# Transmitter_Schematic.net
KiCad netlist of a schematic drawn in Altium Designer
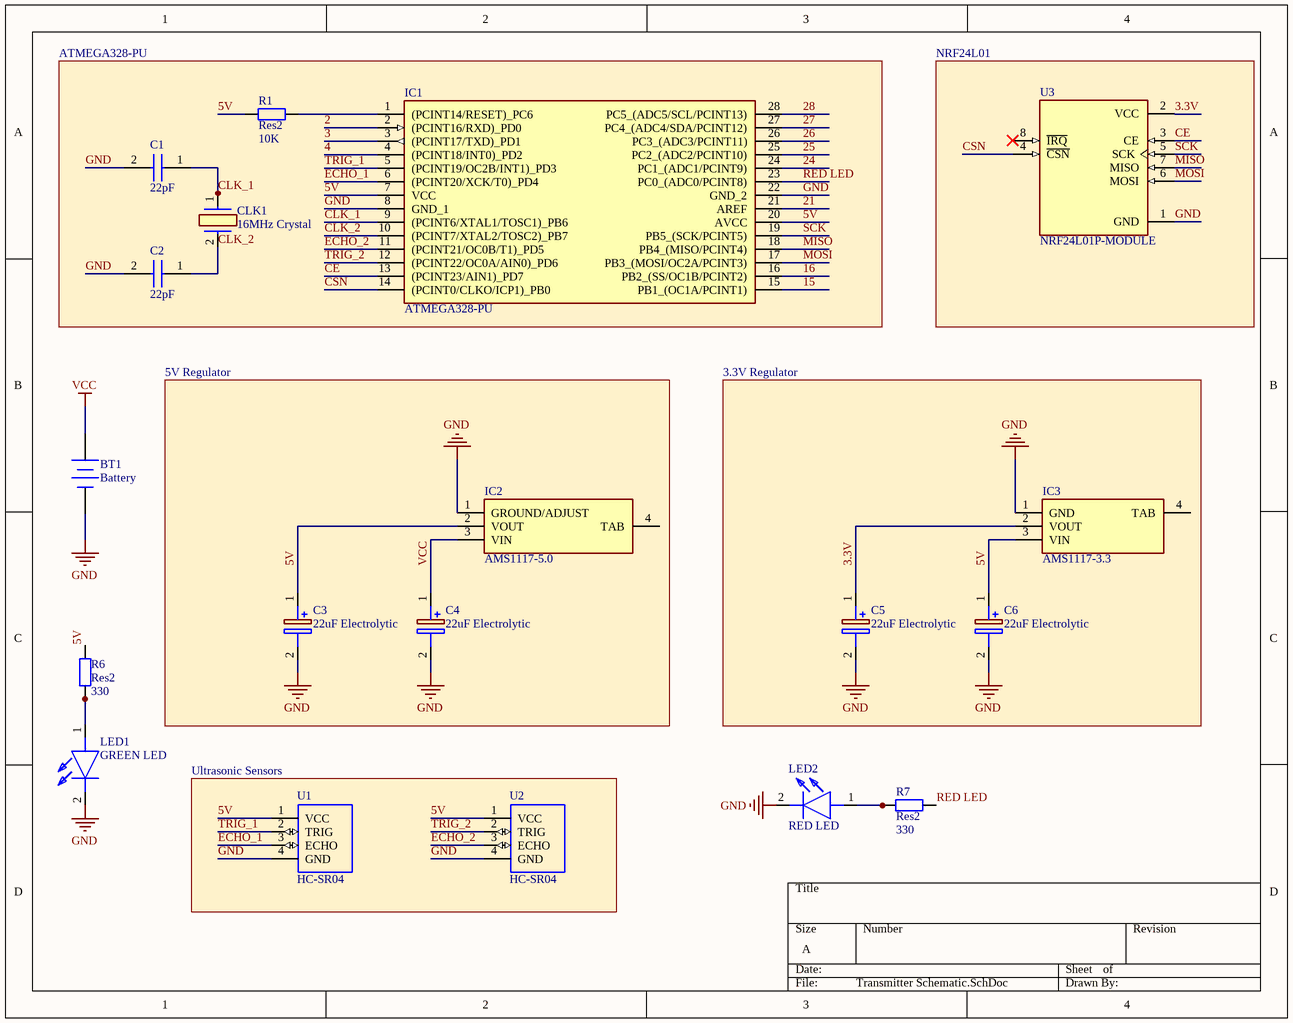
[diagram p0: Transmitter Schematic.SchDoc]

(export (version "E")
  (design (tool "Eeschema 10.0.6"))
  (components
    (comp (ref "BT1")
      (value "Battery")
      (footprint "BAT-2")
      (description "Multicell Battery")
      (fields (field (name "PUBLISHER") "Altium Limited"))
      (libsource (lib "Miscellaneous Devices") (part "Battery"))
    )
    (comp (ref "C1")
      (value "22pF")
      (footprint "SamacSys:S220K25SL0N63L6R")
      (description "Capacitor Ceramic THT")
      (fields
        (field (name "MANUFACTURER_PART_NUMBER") "S220K25SL0N63L6R")
        (field (name "MOUSER PART NUMBER") "594-S220K25SL0N63L6R")
      )
      (libsource (lib "*") (part "S220K25SL0N63L6R"))
    )
    (comp (ref "C2")
      (value "22pF")
      (footprint "SamacSys:S220K25SL0N63L6R")
      (description "Capacitor Ceramic THT")
      (fields
        (field (name "MANUFACTURER_PART_NUMBER") "S220K25SL0N63L6R")
        (field (name "MOUSER PART NUMBER") "594-S220K25SL0N63L6R")
      )
      (libsource (lib "*") (part "S220K25SL0N63L6R"))
    )
    (comp (ref "C3")
      (value "22uF Electrolytic")
      (footprint "SamacSys:CAPPRD250W55D630H1220")
      (description "Capacitor Polarised")
      (fields (field (name "MANUFACTURER_PART_NUMBER") "ECA1EEN220"))
      (libsource (lib "*") (part "ECA1EEN220"))
    )
    (comp (ref "C4")
      (value "22uF Electrolytic")
      (footprint "SamacSys:CAPPRD250W55D630H1220")
      (description "Capacitor Polarised")
      (fields (field (name "MANUFACTURER_PART_NUMBER") "ECA1EEN220"))
      (libsource (lib "*") (part "ECA1EEN220"))
    )
    (comp (ref "C5")
      (value "22uF Electrolytic")
      (footprint "SamacSys:CAPPRD250W55D630H1220")
      (description "Capacitor Polarised")
      (fields (field (name "MANUFACTURER_PART_NUMBER") "ECA1EEN220"))
      (libsource (lib "*") (part "ECA1EEN220"))
    )
    (comp (ref "C6")
      (value "22uF Electrolytic")
      (footprint "SamacSys:CAPPRD250W55D630H1220")
      (description "Capacitor Polarised")
      (fields (field (name "MANUFACTURER_PART_NUMBER") "ECA1EEN220"))
      (libsource (lib "*") (part "ECA1EEN220"))
    )
    (comp (ref "CLK1")
      (value "16MHz Crystal")
      (footprint "SamacSys:LFXTAL036391Bulk")
      (description "Crystal or Oscillator")
      (fields
        (field (name "MANUFACTURER_PART_NUMBER") "LFXTAL036391Bulk")
        (field (name "MOUSER PART NUMBER") "449-LFXTAL036391BULK")
      )
      (libsource (lib "*") (part "LFXTAL036391Bulk"))
    )
    (comp (ref "IC1")
      (value "ATMEGA328-PU")
      (footprint "SamacSys:DIP1016W53P254L3468H457Q28N")
      (description "Integrated Circuit")
      (fields (field (name "MOUSER PART NUMBER") "556-ATMEGA328-PU"))
      (libsource (lib "*") (part "ATMEGA328-PU"))
    )
    (comp (ref "IC2")
      (value "AMS1117-5.0")
      (footprint "SamacSys:SOT229P700X180-4N")
      (description "Integrated Circuit")
      (libsource (lib "*") (part "AMS1117-5.0"))
    )
    (comp (ref "IC3")
      (value "AMS1117-3.3")
      (footprint "SamacSys:SOT229P700X180-4N")
      (description "Integrated Circuit")
      (libsource (lib "*") (part "AMS1117-3.3"))
    )
    (comp (ref "LED1")
      (value "GREEN LED")
      (footprint "SamacSys:125410SURTS530A3")
      (description "LED")
      (fields (field (name "MANUFACTURER_PART_NUMBER") "1254-10SURT/S530-A3"))
      (libsource (lib "*") (part "1254-10SURT_S530-A3"))
    )
    (comp (ref "LED2")
      (value "RED LED")
      (footprint "SamacSys:125410SURTS530A3")
      (description "LED")
      (fields (field (name "MANUFACTURER_PART_NUMBER") "1254-10SURT/S530-A3"))
      (libsource (lib "*") (part "1254-10SURT_S530-A3"))
    )
    (comp (ref "R1")
      (value "Res2")
      (footprint "AXIAL-0.4")
      (description "Resistor")
      (fields (field (name "ALTIUM_VALUE") "10K") (field (name "PUBLISHER") "Altium Limited"))
      (libsource (lib "Miscellaneous Devices") (part "Res2"))
    )
    (comp (ref "R6")
      (value "Res2")
      (footprint "AXIAL-0.4")
      (description "Resistor")
      (fields (field (name "ALTIUM_VALUE") "330") (field (name "PUBLISHER") "Altium Limited"))
      (libsource (lib "") (part "Res2_1"))
    )
    (comp (ref "R7")
      (value "Res2")
      (footprint "AXIAL-0.4")
      (description "Resistor")
      (fields (field (name "ALTIUM_VALUE") "330") (field (name "PUBLISHER") "Altium Limited"))
      (libsource (lib "Miscellaneous Devices") (part "Res2"))
    )
    (comp (ref "U1")
      (value "HC-SR04")
      (footprint "XCVR_HC-SR04")
      (description "Ultrasonic Sensor Module")
      (libsource (lib "HC-SR04") (part "HC-SR04"))
    )
    (comp (ref "U2")
      (value "HC-SR04")
      (footprint "XCVR_HC-SR04")
      (description "Ultrasonic Sensor Module")
      (libsource (lib "HC-SR04") (part "HC-SR04"))
    )
    (comp (ref "U3")
      (value "NRF24L01P-MODULE")
      (footprint "XCVR_NRF24L01P-MODULE-PCB")
      (description "- Transceiver For Use With nRF24L01+")
      (fields (field (name "MP") "NRF24L01P-MODULE-PCB") (field (name "MF") "Nordic Semiconductor"))
      (libsource (lib "NRF24L01P-MODULE-PCB") (part "NRF24L01P-MODULE-PCB"))
    )
  )
  (nets
    (net (code "1") (name "/2") (class "Default")
      (node (ref "IC1") (pin "2") (pinfunction "(PCINT16/RXD)_PD0_2") (pintype "input"))
    )
    (net (code "2") (name "/3") (class "Default")
      (node (ref "IC1") (pin "3") (pinfunction "(PCINT17/TXD)_PD1_3") (pintype "output"))
    )
    (net (code "3") (name "/3.3V") (class "Default")
      (node (ref "C5") (pin "1") (pinfunction "+_1") (pintype "passive"))
      (node (ref "IC3") (pin "2") (pinfunction "VOUT_2") (pintype "passive"))
      (node (ref "U3") (pin "2") (pinfunction "VCC_2") (pintype "power_in"))
    )
    (net (code "4") (name "/4") (class "Default")
      (node (ref "IC1") (pin "4") (pinfunction "(PCINT18/INT0)_PD2_4") (pintype "passive"))
    )
    (net (code "5") (name "/5V") (class "Default")
      (node (ref "C3") (pin "1") (pinfunction "+_1") (pintype "passive"))
      (node (ref "C6") (pin "1") (pinfunction "+_1") (pintype "passive"))
      (node (ref "IC1") (pin "20") (pinfunction "AVCC_20") (pintype "power_in"))
      (node (ref "IC1") (pin "7") (pinfunction "VCC_7") (pintype "power_in"))
      (node (ref "IC2") (pin "2") (pinfunction "VOUT_2") (pintype "passive"))
      (node (ref "IC3") (pin "3") (pinfunction "VIN_3") (pintype "passive"))
      (node (ref "R1") (pin "1") (pinfunction "1_1") (pintype "passive"))
      (node (ref "R6") (pin "2") (pinfunction "2_2") (pintype "passive"))
      (node (ref "U1") (pin "1") (pinfunction "VCC_1") (pintype "power_in"))
      (node (ref "U2") (pin "1") (pinfunction "VCC_1") (pintype "power_in"))
    )
    (net (code "6") (name "/15") (class "Default")
      (node (ref "IC1") (pin "15") (pinfunction "PB1_(OC1A/PCINT1)_15") (pintype "passive"))
    )
    (net (code "7") (name "/16") (class "Default")
      (node (ref "IC1") (pin "16") (pinfunction "PB2_(SS/OC1B/PCINT2)_16") (pintype "passive"))
    )
    (net (code "8") (name "/21") (class "Default")
      (node (ref "IC1") (pin "21") (pinfunction "AREF_21") (pintype "passive"))
    )
    (net (code "9") (name "/24") (class "Default")
      (node (ref "IC1") (pin "24") (pinfunction "PC1_(ADC1/PCINT9)_24") (pintype "passive"))
    )
    (net (code "10") (name "/25") (class "Default")
      (node (ref "IC1") (pin "25") (pinfunction "PC2_(ADC2/PCINT10)_25") (pintype "passive"))
    )
    (net (code "11") (name "/26") (class "Default")
      (node (ref "IC1") (pin "26") (pinfunction "PC3_(ADC3/PCINT11)_26") (pintype "passive"))
    )
    (net (code "12") (name "/27") (class "Default")
      (node (ref "IC1") (pin "27") (pinfunction "PC4_(ADC4/SDA/PCINT12)_27") (pintype "passive"))
    )
    (net (code "13") (name "/28") (class "Default")
      (node (ref "IC1") (pin "28") (pinfunction "PC5_(ADC5/SCL/PCINT13)_28") (pintype "passive"))
    )
    (net (code "14") (name "/CE") (class "Default")
      (node (ref "IC1") (pin "13") (pinfunction "(PCINT23/AIN1)_PD7_13") (pintype "passive"))
      (node (ref "U3") (pin "3") (pinfunction "CE_3") (pintype "input"))
    )
    (net (code "15") (name "/CLK_1") (class "Default")
      (node (ref "C1") (pin "1") (pinfunction "1_1") (pintype "passive"))
      (node (ref "CLK1") (pin "1") (pinfunction "CRYSTAL_1_1") (pintype "passive"))
      (node (ref "IC1") (pin "9") (pinfunction "(PCINT6/XTAL1/TOSC1)_PB6_9") (pintype "passive"))
    )
    (net (code "16") (name "/CLK_2") (class "Default")
      (node (ref "C2") (pin "1") (pinfunction "1_1") (pintype "passive"))
      (node (ref "CLK1") (pin "2") (pinfunction "CRYSTAL_2_2") (pintype "passive"))
      (node (ref "IC1") (pin "10") (pinfunction "(PCINT7/XTAL2/TOSC2)_PB7_10") (pintype "passive"))
    )
    (net (code "17") (name "/CSN") (class "Default")
      (node (ref "IC1") (pin "14") (pinfunction "(PCINT0/CLKO/ICP1)_PB0_14") (pintype "passive"))
      (node (ref "U3") (pin "4") (pinfunction "~{CSN}_4") (pintype "input"))
    )
    (net (code "18") (name "/ECHO_1") (class "Default")
      (node (ref "IC1") (pin "6") (pinfunction "(PCINT20/XCK/T0)_PD4_6") (pintype "passive"))
      (node (ref "U1") (pin "3") (pinfunction "ECHO_3") (pintype "bidirectional"))
    )
    (net (code "19") (name "/ECHO_2") (class "Default")
      (node (ref "IC1") (pin "11") (pinfunction "(PCINT21/OC0B/T1)_PD5_11") (pintype "passive"))
      (node (ref "U2") (pin "3") (pinfunction "ECHO_3") (pintype "bidirectional"))
    )
    (net (code "20") (name "/MISO") (class "Default")
      (node (ref "IC1") (pin "18") (pinfunction "PB4_(MISO/PCINT4)_18") (pintype "passive"))
      (node (ref "U3") (pin "7") (pinfunction "MISO_7") (pintype "input"))
    )
    (net (code "21") (name "/MOSI") (class "Default")
      (node (ref "IC1") (pin "17") (pinfunction "PB3_(MOSI/OC2A/PCINT3)_17") (pintype "passive"))
      (node (ref "U3") (pin "6") (pinfunction "MOSI_6") (pintype "input"))
    )
    (net (code "22") (name "/RED LED") (class "Default")
      (node (ref "IC1") (pin "23") (pinfunction "PC0_(ADC0/PCINT8)_23") (pintype "passive"))
      (node (ref "R7") (pin "2") (pinfunction "2_2") (pintype "passive"))
    )
    (net (code "23") (name "/SCK") (class "Default")
      (node (ref "IC1") (pin "19") (pinfunction "PB5_(SCK/PCINT5)_19") (pintype "passive"))
      (node (ref "U3") (pin "5") (pinfunction "SCK_5") (pintype "input"))
    )
    (net (code "24") (name "/TRIG_1") (class "Default")
      (node (ref "IC1") (pin "5") (pinfunction "(PCINT19/OC2B/INT1)_PD3_5") (pintype "passive"))
      (node (ref "U1") (pin "2") (pinfunction "TRIG_2") (pintype "bidirectional"))
    )
    (net (code "25") (name "/TRIG_2") (class "Default")
      (node (ref "IC1") (pin "12") (pinfunction "(PCINT22/OC0A/AIN0)_PD6_12") (pintype "passive"))
      (node (ref "U2") (pin "2") (pinfunction "TRIG_2") (pintype "bidirectional"))
    )
    (net (code "26") (name "GND") (class "Default")
      (node (ref "BT1") (pin "2") (pinfunction "-_2") (pintype "passive"))
      (node (ref "C1") (pin "2") (pinfunction "2_2") (pintype "passive"))
      (node (ref "C2") (pin "2") (pinfunction "2_2") (pintype "passive"))
      (node (ref "C3") (pin "2") (pinfunction "-_2") (pintype "passive"))
      (node (ref "C4") (pin "2") (pinfunction "-_2") (pintype "passive"))
      (node (ref "C5") (pin "2") (pinfunction "-_2") (pintype "passive"))
      (node (ref "C6") (pin "2") (pinfunction "-_2") (pintype "passive"))
      (node (ref "IC1") (pin "22") (pinfunction "GND_2_22") (pintype "power_in"))
      (node (ref "IC1") (pin "8") (pinfunction "GND_1_8") (pintype "power_in"))
      (node (ref "IC2") (pin "1") (pinfunction "GROUND/ADJUST_1") (pintype "passive"))
      (node (ref "IC3") (pin "1") (pinfunction "GND_1") (pintype "passive"))
      (node (ref "LED1") (pin "2") (pinfunction "K_2") (pintype "passive"))
      (node (ref "LED2") (pin "2") (pinfunction "K_2") (pintype "passive"))
      (node (ref "U1") (pin "4") (pinfunction "GND_4") (pintype "power_in"))
      (node (ref "U2") (pin "4") (pinfunction "GND_4") (pintype "power_in"))
      (node (ref "U3") (pin "1") (pinfunction "GND_1") (pintype "power_in"))
    )
    (net (code "27") (name "Net-(IC1-(PCINT14{slash}RESET)_PC6)") (class "Default")
      (node (ref "IC1") (pin "1") (pinfunction "(PCINT14/RESET)_PC6_1") (pintype "passive"))
      (node (ref "R1") (pin "2") (pinfunction "2_2") (pintype "passive"))
    )
    (net (code "28") (name "Net-(LED1-A)") (class "Default")
      (node (ref "LED1") (pin "1") (pinfunction "A_1") (pintype "passive"))
      (node (ref "R6") (pin "1") (pinfunction "1_1") (pintype "passive"))
    )
    (net (code "29") (name "Net-(LED2-A)") (class "Default")
      (node (ref "LED2") (pin "1") (pinfunction "A_1") (pintype "passive"))
      (node (ref "R7") (pin "1") (pinfunction "1_1") (pintype "passive"))
    )
    (net (code "30") (name "VCC") (class "Default")
      (node (ref "BT1") (pin "1") (pinfunction "+_1") (pintype "passive"))
      (node (ref "C4") (pin "1") (pinfunction "+_1") (pintype "passive"))
      (node (ref "IC2") (pin "3") (pinfunction "VIN_3") (pintype "passive"))
    )
    (net (code "31") (name "unconnected-(IC2-TAB-Pad4)") (class "Default")
      (node (ref "IC2") (pin "4") (pinfunction "TAB_4") (pintype "passive"))
    )
    (net (code "32") (name "unconnected-(IC3-TAB-Pad4)") (class "Default")
      (node (ref "IC3") (pin "4") (pinfunction "TAB_4") (pintype "passive"))
    )
    (net (code "33") (name "unconnected-(U3-~{IRQ}-Pad8)") (class "Default")
      (node (ref "U3") (pin "8") (pinfunction "~{IRQ}_8") (pintype "input+no_connect"))
    )
  )
)
